# score_anzeige.net
KiCad netlist of a schematic drawn in EAGLE
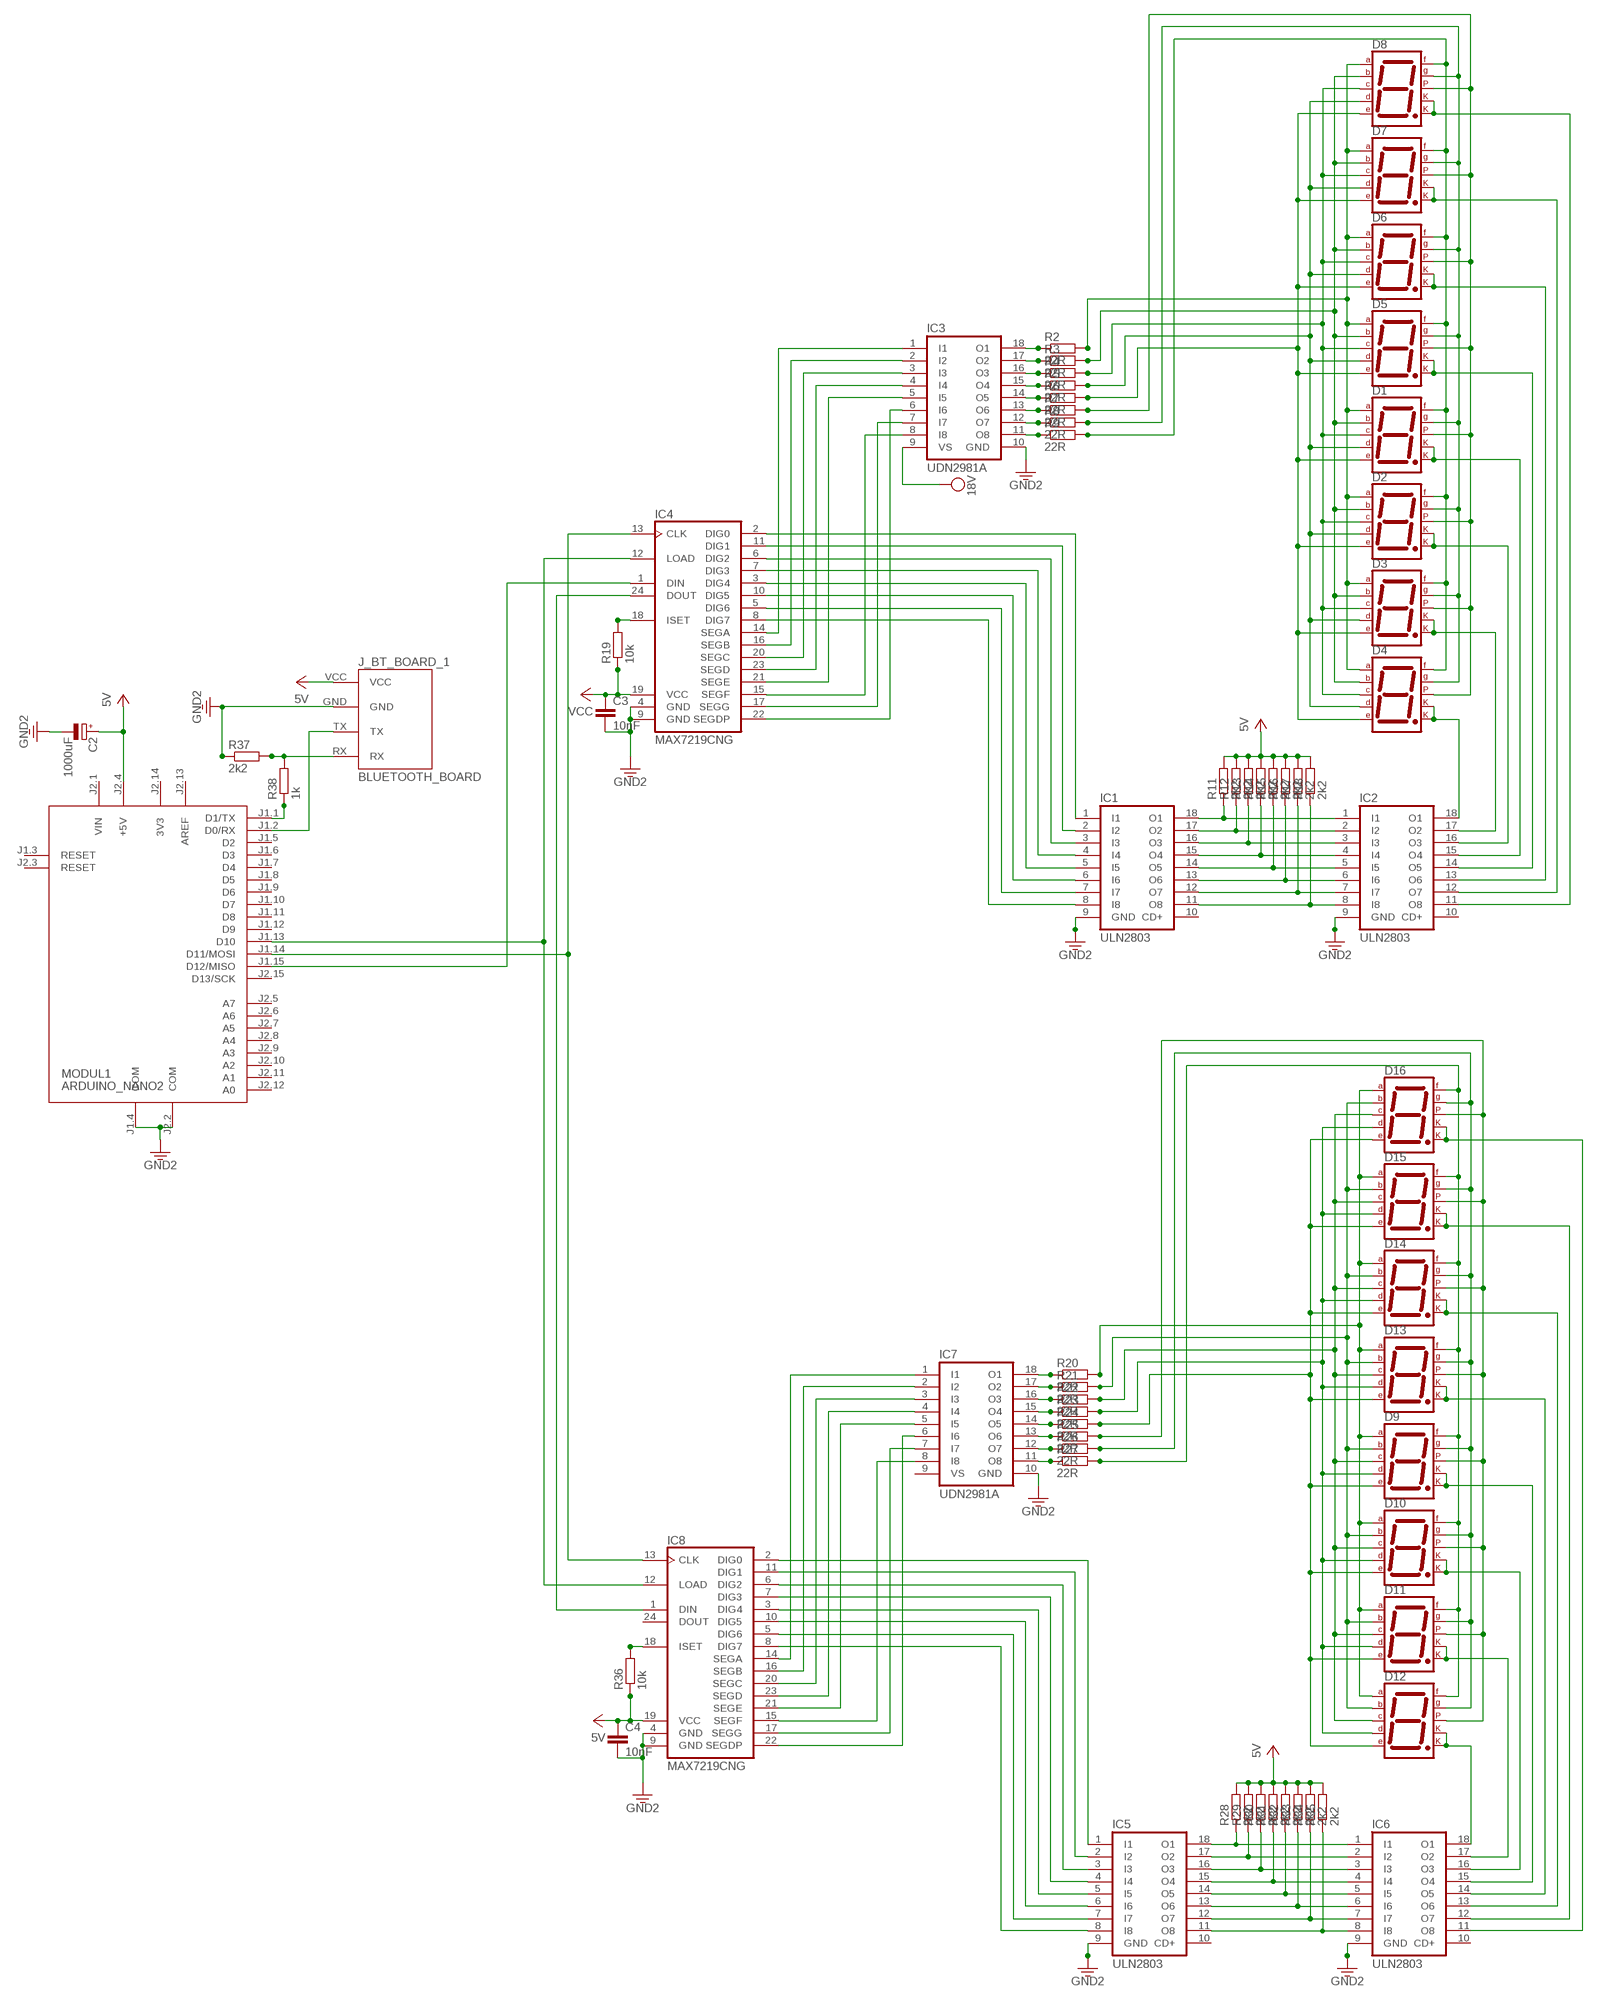
[diagram p0: schematic, sheet 1]

(export (version "E")
  (design (tool "Eeschema 10.0.6"))
  (components
    (comp (ref "C2")
      (value "1000uF")
      (footprint "eagle-import:E5-10,5")
      (libsource (lib "eagle-import") (part "CPOL-EUE5-10.5"))
    )
    (comp (ref "C3")
      (value "10nF")
      (footprint "eagle-import:C025-025X050")
      (libsource (lib "eagle-import") (part "C-EU025-025X050"))
    )
    (comp (ref "C4")
      (value "10nF")
      (footprint "eagle-import:C025-025X050")
      (libsource (lib "eagle-import") (part "C-EU025-025X050"))
    )
    (comp (ref "D1")
      (value "7SEG-MCK")
      (footprint "eagle-import:7SEG-7")
      (libsource (lib "eagle-import") (part "7SEG-MCK"))
    )
    (comp (ref "D2")
      (value "7SEG-MCK")
      (footprint "eagle-import:7SEG-7")
      (libsource (lib "eagle-import") (part "7SEG-MCK"))
    )
    (comp (ref "D3")
      (value "7SEG-MCK")
      (footprint "eagle-import:7SEG-7")
      (libsource (lib "eagle-import") (part "7SEG-MCK"))
    )
    (comp (ref "D4")
      (value "7SEG-MCK")
      (footprint "eagle-import:7SEG-7")
      (libsource (lib "eagle-import") (part "7SEG-MCK"))
    )
    (comp (ref "D5")
      (value "7SEG-MCK")
      (footprint "eagle-import:7SEG-7")
      (libsource (lib "eagle-import") (part "7SEG-MCK"))
    )
    (comp (ref "D6")
      (value "7SEG-MCK")
      (footprint "eagle-import:7SEG-7")
      (libsource (lib "eagle-import") (part "7SEG-MCK"))
    )
    (comp (ref "D7")
      (value "7SEG-MCK")
      (footprint "eagle-import:7SEG-7")
      (libsource (lib "eagle-import") (part "7SEG-MCK"))
    )
    (comp (ref "D8")
      (value "7SEG-MCK")
      (footprint "eagle-import:7SEG-7")
      (libsource (lib "eagle-import") (part "7SEG-MCK"))
    )
    (comp (ref "D9")
      (value "7SEG-MCK")
      (footprint "eagle-import:7SEG-7")
      (libsource (lib "eagle-import") (part "7SEG-MCK"))
    )
    (comp (ref "D10")
      (value "7SEG-MCK")
      (footprint "eagle-import:7SEG-7")
      (libsource (lib "eagle-import") (part "7SEG-MCK"))
    )
    (comp (ref "D11")
      (value "7SEG-MCK")
      (footprint "eagle-import:7SEG-7")
      (libsource (lib "eagle-import") (part "7SEG-MCK"))
    )
    (comp (ref "D12")
      (value "7SEG-MCK")
      (footprint "eagle-import:7SEG-7")
      (libsource (lib "eagle-import") (part "7SEG-MCK"))
    )
    (comp (ref "D13")
      (value "7SEG-MCK")
      (footprint "eagle-import:7SEG-7")
      (libsource (lib "eagle-import") (part "7SEG-MCK"))
    )
    (comp (ref "D14")
      (value "7SEG-MCK")
      (footprint "eagle-import:7SEG-7")
      (libsource (lib "eagle-import") (part "7SEG-MCK"))
    )
    (comp (ref "D15")
      (value "7SEG-MCK")
      (footprint "eagle-import:7SEG-7")
      (libsource (lib "eagle-import") (part "7SEG-MCK"))
    )
    (comp (ref "D16")
      (value "7SEG-MCK")
      (footprint "eagle-import:7SEG-7")
      (libsource (lib "eagle-import") (part "7SEG-MCK"))
    )
    (comp (ref "IC1")
      (value "ULN2803")
      (footprint "eagle-import:DIL18")
      (libsource (lib "eagle-import") (part "ULN2803A"))
    )
    (comp (ref "IC2")
      (value "ULN2803")
      (footprint "eagle-import:DIL18")
      (libsource (lib "eagle-import") (part "ULN2803A"))
    )
    (comp (ref "IC3")
      (value "UDN2981A")
      (footprint "eagle-import:DIL18")
      (libsource (lib "eagle-import") (part "UDN298A1"))
    )
    (comp (ref "IC4")
      (value "MAX7219CNG")
      (footprint "eagle-import:DIL24-3")
      (fields (field (name "MF") "MAXIM"))
      (libsource (lib "eagle-import") (part "MAX7219CNG"))
    )
    (comp (ref "IC5")
      (value "ULN2803")
      (footprint "eagle-import:DIL18")
      (libsource (lib "eagle-import") (part "ULN2803A"))
    )
    (comp (ref "IC6")
      (value "ULN2803")
      (footprint "eagle-import:DIL18")
      (libsource (lib "eagle-import") (part "ULN2803A"))
    )
    (comp (ref "IC7")
      (value "UDN2981A")
      (footprint "eagle-import:DIL18")
      (libsource (lib "eagle-import") (part "UDN298A1"))
    )
    (comp (ref "IC8")
      (value "MAX7219CNG")
      (footprint "eagle-import:DIL24-3")
      (fields (field (name "MF") "MAXIM"))
      (libsource (lib "eagle-import") (part "MAX7219CNG"))
    )
    (comp (ref "J_BT_BOARD_1")
      (value "BLUETOOTH_BOARD")
      (footprint "eagle-import:BT_BOARD_FOOTPRINT")
      (libsource (lib "eagle-import") (part "BLUETOOTH_BOARD"))
    )
    (comp (ref "MODUL1")
      (value "ARDUINO_NANO2")
      (footprint "eagle-import:ARDUINO_NANO2")
      (libsource (lib "eagle-import") (part "ARDUINO_NANO2"))
    )
    (comp (ref "R2")
      (value "22R")
      (footprint "eagle-import:0204_7")
      (libsource (lib "eagle-import") (part "R-EU_0204/7"))
    )
    (comp (ref "R3")
      (value "22R")
      (footprint "eagle-import:0204_7")
      (libsource (lib "eagle-import") (part "R-EU_0204/7"))
    )
    (comp (ref "R4")
      (value "22R")
      (footprint "eagle-import:0204_7")
      (libsource (lib "eagle-import") (part "R-EU_0204/7"))
    )
    (comp (ref "R5")
      (value "22R")
      (footprint "eagle-import:0204_7")
      (libsource (lib "eagle-import") (part "R-EU_0204/7"))
    )
    (comp (ref "R6")
      (value "22R")
      (footprint "eagle-import:0204_7")
      (libsource (lib "eagle-import") (part "R-EU_0204/7"))
    )
    (comp (ref "R7")
      (value "22R")
      (footprint "eagle-import:0204_7")
      (libsource (lib "eagle-import") (part "R-EU_0204/7"))
    )
    (comp (ref "R8")
      (value "22R")
      (footprint "eagle-import:0204_7")
      (libsource (lib "eagle-import") (part "R-EU_0204/7"))
    )
    (comp (ref "R9")
      (value "22R")
      (footprint "eagle-import:0204_7")
      (libsource (lib "eagle-import") (part "R-EU_0204/7"))
    )
    (comp (ref "R11")
      (value "2k2")
      (footprint "eagle-import:0204_7")
      (libsource (lib "eagle-import") (part "R-EU_0204/7"))
    )
    (comp (ref "R12")
      (value "2k2")
      (footprint "eagle-import:0204_7")
      (libsource (lib "eagle-import") (part "R-EU_0204/7"))
    )
    (comp (ref "R13")
      (value "2k2")
      (footprint "eagle-import:0204_7")
      (libsource (lib "eagle-import") (part "R-EU_0204/7"))
    )
    (comp (ref "R14")
      (value "2k2")
      (footprint "eagle-import:0204_7")
      (libsource (lib "eagle-import") (part "R-EU_0204/7"))
    )
    (comp (ref "R15")
      (value "2k2")
      (footprint "eagle-import:0204_7")
      (libsource (lib "eagle-import") (part "R-EU_0204/7"))
    )
    (comp (ref "R16")
      (value "2k2")
      (footprint "eagle-import:0204_7")
      (libsource (lib "eagle-import") (part "R-EU_0204/7"))
    )
    (comp (ref "R17")
      (value "2k2")
      (footprint "eagle-import:0204_7")
      (libsource (lib "eagle-import") (part "R-EU_0204/7"))
    )
    (comp (ref "R18")
      (value "2k2")
      (footprint "eagle-import:0204_7")
      (libsource (lib "eagle-import") (part "R-EU_0204/7"))
    )
    (comp (ref "R19")
      (value "10k")
      (footprint "eagle-import:0204_7")
      (libsource (lib "eagle-import") (part "R-EU_0204/7"))
    )
    (comp (ref "R20")
      (value "22R")
      (footprint "eagle-import:0204_7")
      (libsource (lib "eagle-import") (part "R-EU_0204/7"))
    )
    (comp (ref "R21")
      (value "22R")
      (footprint "eagle-import:0204_7")
      (libsource (lib "eagle-import") (part "R-EU_0204/7"))
    )
    (comp (ref "R22")
      (value "22R")
      (footprint "eagle-import:0204_7")
      (libsource (lib "eagle-import") (part "R-EU_0204/7"))
    )
    (comp (ref "R23")
      (value "22R")
      (footprint "eagle-import:0204_7")
      (libsource (lib "eagle-import") (part "R-EU_0204/7"))
    )
    (comp (ref "R24")
      (value "22R")
      (footprint "eagle-import:0204_7")
      (libsource (lib "eagle-import") (part "R-EU_0204/7"))
    )
    (comp (ref "R25")
      (value "22R")
      (footprint "eagle-import:0204_7")
      (libsource (lib "eagle-import") (part "R-EU_0204/7"))
    )
    (comp (ref "R26")
      (value "22R")
      (footprint "eagle-import:0204_7")
      (libsource (lib "eagle-import") (part "R-EU_0204/7"))
    )
    (comp (ref "R27")
      (value "22R")
      (footprint "eagle-import:0204_7")
      (libsource (lib "eagle-import") (part "R-EU_0204/7"))
    )
    (comp (ref "R28")
      (value "2k2")
      (footprint "eagle-import:0204_7")
      (libsource (lib "eagle-import") (part "R-EU_0204/7"))
    )
    (comp (ref "R29")
      (value "2k2")
      (footprint "eagle-import:0204_7")
      (libsource (lib "eagle-import") (part "R-EU_0204/7"))
    )
    (comp (ref "R30")
      (value "2k2")
      (footprint "eagle-import:0204_7")
      (libsource (lib "eagle-import") (part "R-EU_0204/7"))
    )
    (comp (ref "R31")
      (value "2k2")
      (footprint "eagle-import:0204_7")
      (libsource (lib "eagle-import") (part "R-EU_0204/7"))
    )
    (comp (ref "R32")
      (value "2k2")
      (footprint "eagle-import:0204_7")
      (libsource (lib "eagle-import") (part "R-EU_0204/7"))
    )
    (comp (ref "R33")
      (value "2k2")
      (footprint "eagle-import:0204_7")
      (libsource (lib "eagle-import") (part "R-EU_0204/7"))
    )
    (comp (ref "R34")
      (value "2k2")
      (footprint "eagle-import:0204_7")
      (libsource (lib "eagle-import") (part "R-EU_0204/7"))
    )
    (comp (ref "R35")
      (value "2k2")
      (footprint "eagle-import:0204_7")
      (libsource (lib "eagle-import") (part "R-EU_0204/7"))
    )
    (comp (ref "R36")
      (value "10k")
      (footprint "eagle-import:0204_7")
      (libsource (lib "eagle-import") (part "R-EU_0204/7"))
    )
    (comp (ref "R37")
      (value "2k2")
      (footprint "eagle-import:0204_7")
      (libsource (lib "eagle-import") (part "R-EU_0204/7"))
    )
    (comp (ref "R38")
      (value "1k")
      (footprint "eagle-import:0204_7")
      (libsource (lib "eagle-import") (part "R-EU_0204/7"))
    )
  )
  (nets
    (net (code "1") (name "/3V3") (class "Default")
      (node (ref "MODUL1") (pin "J2.14") (pinfunction "3V3_J2.14") (pintype "power_in"))
    )
    (net (code "2") (name "/AREF") (class "Default")
      (node (ref "MODUL1") (pin "J2.13") (pinfunction "AREF_J2.13") (pintype "power_in"))
    )
    (net (code "3") (name "/VIN") (class "Default")
      (node (ref "MODUL1") (pin "J2.1") (pinfunction "VIN_J2.1") (pintype "power_in"))
    )
    (net (code "4") (name "18V") (class "Default")
      (node (ref "C2") (pin "+") (pinfunction "+_+") (pintype "passive"))
      (node (ref "C3") (pin "1") (pinfunction "1_1") (pintype "passive"))
      (node (ref "C4") (pin "1") (pinfunction "1_1") (pintype "passive"))
      (node (ref "IC3") (pin "9") (pinfunction "VS_9") (pintype "passive"))
      (node (ref "IC4") (pin "19") (pinfunction "VCC_19") (pintype "power_in"))
      (node (ref "IC8") (pin "19") (pinfunction "VCC_19") (pintype "power_in"))
      (node (ref "J_BT_BOARD_1") (pin "VCC") (pinfunction "VCC_VCC") (pintype "bidirectional"))
      (node (ref "MODUL1") (pin "J2.4") (pinfunction "+5V_J2.4") (pintype "power_in"))
      (node (ref "R11") (pin "2") (pinfunction "2_2") (pintype "passive"))
      (node (ref "R12") (pin "2") (pinfunction "2_2") (pintype "passive"))
      (node (ref "R13") (pin "2") (pinfunction "2_2") (pintype "passive"))
      (node (ref "R14") (pin "2") (pinfunction "2_2") (pintype "passive"))
      (node (ref "R15") (pin "2") (pinfunction "2_2") (pintype "passive"))
      (node (ref "R16") (pin "2") (pinfunction "2_2") (pintype "passive"))
      (node (ref "R17") (pin "2") (pinfunction "2_2") (pintype "passive"))
      (node (ref "R18") (pin "2") (pinfunction "2_2") (pintype "passive"))
      (node (ref "R19") (pin "1") (pinfunction "1_1") (pintype "passive"))
      (node (ref "R28") (pin "2") (pinfunction "2_2") (pintype "passive"))
      (node (ref "R29") (pin "2") (pinfunction "2_2") (pintype "passive"))
      (node (ref "R30") (pin "2") (pinfunction "2_2") (pintype "passive"))
      (node (ref "R31") (pin "2") (pinfunction "2_2") (pintype "passive"))
      (node (ref "R32") (pin "2") (pinfunction "2_2") (pintype "passive"))
      (node (ref "R33") (pin "2") (pinfunction "2_2") (pintype "passive"))
      (node (ref "R34") (pin "2") (pinfunction "2_2") (pintype "passive"))
      (node (ref "R35") (pin "2") (pinfunction "2_2") (pintype "passive"))
      (node (ref "R36") (pin "1") (pinfunction "1_1") (pintype "passive"))
    )
    (net (code "5") (name "GND2") (class "Default")
      (node (ref "C2") (pin "-") (pinfunction "-_-") (pintype "passive"))
      (node (ref "C3") (pin "2") (pinfunction "2_2") (pintype "passive"))
      (node (ref "C4") (pin "2") (pinfunction "2_2") (pintype "passive"))
      (node (ref "IC1") (pin "9") (pinfunction "GND_9") (pintype "power_in"))
      (node (ref "IC2") (pin "9") (pinfunction "GND_9") (pintype "power_in"))
      (node (ref "IC3") (pin "10") (pinfunction "GND_10") (pintype "power_in"))
      (node (ref "IC4") (pin "4") (pinfunction "GND_4") (pintype "power_in"))
      (node (ref "IC4") (pin "9") (pinfunction "GND_9") (pintype "power_in"))
      (node (ref "IC5") (pin "9") (pinfunction "GND_9") (pintype "power_in"))
      (node (ref "IC6") (pin "9") (pinfunction "GND_9") (pintype "power_in"))
      (node (ref "IC7") (pin "10") (pinfunction "GND_10") (pintype "power_in"))
      (node (ref "IC8") (pin "4") (pinfunction "GND_4") (pintype "power_in"))
      (node (ref "IC8") (pin "9") (pinfunction "GND_9") (pintype "power_in"))
      (node (ref "J_BT_BOARD_1") (pin "GND") (pinfunction "GND_GND") (pintype "bidirectional"))
      (node (ref "MODUL1") (pin "J1.4") (pinfunction "COM_J1.4") (pintype "power_in"))
      (node (ref "MODUL1") (pin "J2.2") (pinfunction "COM_J2.2") (pintype "power_in"))
      (node (ref "R37") (pin "1") (pinfunction "1_1") (pintype "passive"))
    )
    (net (code "6") (name "Net-(D1-A)") (class "Default")
      (node (ref "D1") (pin "10") (pinfunction "A_10") (pintype "passive"))
      (node (ref "D2") (pin "10") (pinfunction "A_10") (pintype "passive"))
      (node (ref "D3") (pin "10") (pinfunction "A_10") (pintype "passive"))
      (node (ref "D4") (pin "10") (pinfunction "A_10") (pintype "passive"))
      (node (ref "D5") (pin "10") (pinfunction "A_10") (pintype "passive"))
      (node (ref "D6") (pin "10") (pinfunction "A_10") (pintype "passive"))
      (node (ref "D7") (pin "10") (pinfunction "A_10") (pintype "passive"))
      (node (ref "D8") (pin "10") (pinfunction "A_10") (pintype "passive"))
      (node (ref "R2") (pin "2") (pinfunction "2_2") (pintype "passive"))
    )
    (net (code "7") (name "Net-(D1-B)") (class "Default")
      (node (ref "D1") (pin "9") (pinfunction "B_9") (pintype "passive"))
      (node (ref "D2") (pin "9") (pinfunction "B_9") (pintype "passive"))
      (node (ref "D3") (pin "9") (pinfunction "B_9") (pintype "passive"))
      (node (ref "D4") (pin "9") (pinfunction "B_9") (pintype "passive"))
      (node (ref "D5") (pin "9") (pinfunction "B_9") (pintype "passive"))
      (node (ref "D6") (pin "9") (pinfunction "B_9") (pintype "passive"))
      (node (ref "D7") (pin "9") (pinfunction "B_9") (pintype "passive"))
      (node (ref "D8") (pin "9") (pinfunction "B_9") (pintype "passive"))
      (node (ref "R3") (pin "2") (pinfunction "2_2") (pintype "passive"))
    )
    (net (code "8") (name "Net-(D1-C)") (class "Default")
      (node (ref "D1") (pin "8") (pinfunction "C_8") (pintype "passive"))
      (node (ref "D2") (pin "8") (pinfunction "C_8") (pintype "passive"))
      (node (ref "D3") (pin "8") (pinfunction "C_8") (pintype "passive"))
      (node (ref "D4") (pin "8") (pinfunction "C_8") (pintype "passive"))
      (node (ref "D5") (pin "8") (pinfunction "C_8") (pintype "passive"))
      (node (ref "D6") (pin "8") (pinfunction "C_8") (pintype "passive"))
      (node (ref "D7") (pin "8") (pinfunction "C_8") (pintype "passive"))
      (node (ref "D8") (pin "8") (pinfunction "C_8") (pintype "passive"))
      (node (ref "R4") (pin "2") (pinfunction "2_2") (pintype "passive"))
    )
    (net (code "9") (name "Net-(D1-CK1)") (class "Default")
      (node (ref "D1") (pin "1") (pinfunction "CK1_1") (pintype "passive"))
      (node (ref "D1") (pin "6") (pinfunction "CK2_6") (pintype "passive"))
      (node (ref "IC2") (pin "15") (pinfunction "O4_15") (pintype "open_collector"))
    )
    (net (code "10") (name "Net-(D1-D)") (class "Default")
      (node (ref "D1") (pin "5") (pinfunction "D_5") (pintype "passive"))
      (node (ref "D2") (pin "5") (pinfunction "D_5") (pintype "passive"))
      (node (ref "D3") (pin "5") (pinfunction "D_5") (pintype "passive"))
      (node (ref "D4") (pin "5") (pinfunction "D_5") (pintype "passive"))
      (node (ref "D5") (pin "5") (pinfunction "D_5") (pintype "passive"))
      (node (ref "D6") (pin "5") (pinfunction "D_5") (pintype "passive"))
      (node (ref "D7") (pin "5") (pinfunction "D_5") (pintype "passive"))
      (node (ref "D8") (pin "5") (pinfunction "D_5") (pintype "passive"))
      (node (ref "R5") (pin "2") (pinfunction "2_2") (pintype "passive"))
    )
    (net (code "11") (name "Net-(D1-DP)") (class "Default")
      (node (ref "D1") (pin "7") (pinfunction "DP_7") (pintype "passive"))
      (node (ref "D2") (pin "7") (pinfunction "DP_7") (pintype "passive"))
      (node (ref "D3") (pin "7") (pinfunction "DP_7") (pintype "passive"))
      (node (ref "D4") (pin "7") (pinfunction "DP_7") (pintype "passive"))
      (node (ref "D5") (pin "7") (pinfunction "DP_7") (pintype "passive"))
      (node (ref "D6") (pin "7") (pinfunction "DP_7") (pintype "passive"))
      (node (ref "D7") (pin "7") (pinfunction "DP_7") (pintype "passive"))
      (node (ref "D8") (pin "7") (pinfunction "DP_7") (pintype "passive"))
      (node (ref "R7") (pin "2") (pinfunction "2_2") (pintype "passive"))
    )
    (net (code "12") (name "Net-(D1-E)") (class "Default")
      (node (ref "D1") (pin "4") (pinfunction "E_4") (pintype "passive"))
      (node (ref "D2") (pin "4") (pinfunction "E_4") (pintype "passive"))
      (node (ref "D3") (pin "4") (pinfunction "E_4") (pintype "passive"))
      (node (ref "D4") (pin "4") (pinfunction "E_4") (pintype "passive"))
      (node (ref "D5") (pin "4") (pinfunction "E_4") (pintype "passive"))
      (node (ref "D6") (pin "4") (pinfunction "E_4") (pintype "passive"))
      (node (ref "D7") (pin "4") (pinfunction "E_4") (pintype "passive"))
      (node (ref "D8") (pin "4") (pinfunction "E_4") (pintype "passive"))
      (node (ref "R6") (pin "2") (pinfunction "2_2") (pintype "passive"))
    )
    (net (code "13") (name "Net-(D1-F)") (class "Default")
      (node (ref "D1") (pin "2") (pinfunction "F_2") (pintype "passive"))
      (node (ref "D2") (pin "2") (pinfunction "F_2") (pintype "passive"))
      (node (ref "D3") (pin "2") (pinfunction "F_2") (pintype "passive"))
      (node (ref "D4") (pin "2") (pinfunction "F_2") (pintype "passive"))
      (node (ref "D5") (pin "2") (pinfunction "F_2") (pintype "passive"))
      (node (ref "D6") (pin "2") (pinfunction "F_2") (pintype "passive"))
      (node (ref "D7") (pin "2") (pinfunction "F_2") (pintype "passive"))
      (node (ref "D8") (pin "2") (pinfunction "F_2") (pintype "passive"))
      (node (ref "R9") (pin "2") (pinfunction "2_2") (pintype "passive"))
    )
    (net (code "14") (name "Net-(D1-G)") (class "Default")
      (node (ref "D1") (pin "3") (pinfunction "G_3") (pintype "passive"))
      (node (ref "D2") (pin "3") (pinfunction "G_3") (pintype "passive"))
      (node (ref "D3") (pin "3") (pinfunction "G_3") (pintype "passive"))
      (node (ref "D4") (pin "3") (pinfunction "G_3") (pintype "passive"))
      (node (ref "D5") (pin "3") (pinfunction "G_3") (pintype "passive"))
      (node (ref "D6") (pin "3") (pinfunction "G_3") (pintype "passive"))
      (node (ref "D7") (pin "3") (pinfunction "G_3") (pintype "passive"))
      (node (ref "D8") (pin "3") (pinfunction "G_3") (pintype "passive"))
      (node (ref "R8") (pin "2") (pinfunction "2_2") (pintype "passive"))
    )
    (net (code "15") (name "Net-(D2-CK1)") (class "Default")
      (node (ref "D2") (pin "1") (pinfunction "CK1_1") (pintype "passive"))
      (node (ref "D2") (pin "6") (pinfunction "CK2_6") (pintype "passive"))
      (node (ref "IC2") (pin "16") (pinfunction "O3_16") (pintype "open_collector"))
    )
    (net (code "16") (name "Net-(D3-CK1)") (class "Default")
      (node (ref "D3") (pin "1") (pinfunction "CK1_1") (pintype "passive"))
      (node (ref "D3") (pin "6") (pinfunction "CK2_6") (pintype "passive"))
      (node (ref "IC2") (pin "17") (pinfunction "O2_17") (pintype "open_collector"))
    )
    (net (code "17") (name "Net-(D4-CK1)") (class "Default")
      (node (ref "D4") (pin "1") (pinfunction "CK1_1") (pintype "passive"))
      (node (ref "D4") (pin "6") (pinfunction "CK2_6") (pintype "passive"))
      (node (ref "IC2") (pin "18") (pinfunction "O1_18") (pintype "open_collector"))
    )
    (net (code "18") (name "Net-(D5-CK1)") (class "Default")
      (node (ref "D5") (pin "1") (pinfunction "CK1_1") (pintype "passive"))
      (node (ref "D5") (pin "6") (pinfunction "CK2_6") (pintype "passive"))
      (node (ref "IC2") (pin "14") (pinfunction "O5_14") (pintype "open_collector"))
    )
    (net (code "19") (name "Net-(D6-CK1)") (class "Default")
      (node (ref "D6") (pin "1") (pinfunction "CK1_1") (pintype "passive"))
      (node (ref "D6") (pin "6") (pinfunction "CK2_6") (pintype "passive"))
      (node (ref "IC2") (pin "13") (pinfunction "O6_13") (pintype "open_collector"))
    )
    (net (code "20") (name "Net-(D7-CK1)") (class "Default")
      (node (ref "D7") (pin "1") (pinfunction "CK1_1") (pintype "passive"))
      (node (ref "D7") (pin "6") (pinfunction "CK2_6") (pintype "passive"))
      (node (ref "IC2") (pin "12") (pinfunction "O7_12") (pintype "open_collector"))
    )
    (net (code "21") (name "Net-(D8-CK1)") (class "Default")
      (node (ref "D8") (pin "1") (pinfunction "CK1_1") (pintype "passive"))
      (node (ref "D8") (pin "6") (pinfunction "CK2_6") (pintype "passive"))
      (node (ref "IC2") (pin "11") (pinfunction "O8_11") (pintype "open_collector"))
    )
    (net (code "22") (name "Net-(D9-CK1)") (class "Default")
      (node (ref "D9") (pin "1") (pinfunction "CK1_1") (pintype "passive"))
      (node (ref "D9") (pin "6") (pinfunction "CK2_6") (pintype "passive"))
      (node (ref "IC6") (pin "15") (pinfunction "O4_15") (pintype "open_collector"))
    )
    (net (code "23") (name "Net-(D10-A)") (class "Default")
      (node (ref "D10") (pin "10") (pinfunction "A_10") (pintype "passive"))
      (node (ref "D11") (pin "10") (pinfunction "A_10") (pintype "passive"))
      (node (ref "D12") (pin "10") (pinfunction "A_10") (pintype "passive"))
      (node (ref "D13") (pin "10") (pinfunction "A_10") (pintype "passive"))
      (node (ref "D14") (pin "10") (pinfunction "A_10") (pintype "passive"))
      (node (ref "D15") (pin "10") (pinfunction "A_10") (pintype "passive"))
      (node (ref "D16") (pin "10") (pinfunction "A_10") (pintype "passive"))
      (node (ref "D9") (pin "10") (pinfunction "A_10") (pintype "passive"))
      (node (ref "R20") (pin "2") (pinfunction "2_2") (pintype "passive"))
    )
    (net (code "24") (name "Net-(D10-B)") (class "Default")
      (node (ref "D10") (pin "9") (pinfunction "B_9") (pintype "passive"))
      (node (ref "D11") (pin "9") (pinfunction "B_9") (pintype "passive"))
      (node (ref "D12") (pin "9") (pinfunction "B_9") (pintype "passive"))
      (node (ref "D13") (pin "9") (pinfunction "B_9") (pintype "passive"))
      (node (ref "D14") (pin "9") (pinfunction "B_9") (pintype "passive"))
      (node (ref "D15") (pin "9") (pinfunction "B_9") (pintype "passive"))
      (node (ref "D16") (pin "9") (pinfunction "B_9") (pintype "passive"))
      (node (ref "D9") (pin "9") (pinfunction "B_9") (pintype "passive"))
      (node (ref "R21") (pin "2") (pinfunction "2_2") (pintype "passive"))
    )
    (net (code "25") (name "Net-(D10-C)") (class "Default")
      (node (ref "D10") (pin "8") (pinfunction "C_8") (pintype "passive"))
      (node (ref "D11") (pin "8") (pinfunction "C_8") (pintype "passive"))
      (node (ref "D12") (pin "8") (pinfunction "C_8") (pintype "passive"))
      (node (ref "D13") (pin "8") (pinfunction "C_8") (pintype "passive"))
      (node (ref "D14") (pin "8") (pinfunction "C_8") (pintype "passive"))
      (node (ref "D15") (pin "8") (pinfunction "C_8") (pintype "passive"))
      (node (ref "D16") (pin "8") (pinfunction "C_8") (pintype "passive"))
      (node (ref "D9") (pin "8") (pinfunction "C_8") (pintype "passive"))
      (node (ref "R22") (pin "2") (pinfunction "2_2") (pintype "passive"))
    )
    (net (code "26") (name "Net-(D10-CK1)") (class "Default")
      (node (ref "D10") (pin "1") (pinfunction "CK1_1") (pintype "passive"))
      (node (ref "D10") (pin "6") (pinfunction "CK2_6") (pintype "passive"))
      (node (ref "IC6") (pin "16") (pinfunction "O3_16") (pintype "open_collector"))
    )
    (net (code "27") (name "Net-(D10-D)") (class "Default")
      (node (ref "D10") (pin "5") (pinfunction "D_5") (pintype "passive"))
      (node (ref "D11") (pin "5") (pinfunction "D_5") (pintype "passive"))
      (node (ref "D12") (pin "5") (pinfunction "D_5") (pintype "passive"))
      (node (ref "D13") (pin "5") (pinfunction "D_5") (pintype "passive"))
      (node (ref "D14") (pin "5") (pinfunction "D_5") (pintype "passive"))
      (node (ref "D15") (pin "5") (pinfunction "D_5") (pintype "passive"))
      (node (ref "D16") (pin "5") (pinfunction "D_5") (pintype "passive"))
      (node (ref "D9") (pin "5") (pinfunction "D_5") (pintype "passive"))
      (node (ref "R23") (pin "2") (pinfunction "2_2") (pintype "passive"))
    )
    (net (code "28") (name "Net-(D10-DP)") (class "Default")
      (node (ref "D10") (pin "7") (pinfunction "DP_7") (pintype "passive"))
      (node (ref "D11") (pin "7") (pinfunction "DP_7") (pintype "passive"))
      (node (ref "D12") (pin "7") (pinfunction "DP_7") (pintype "passive"))
      (node (ref "D13") (pin "7") (pinfunction "DP_7") (pintype "passive"))
      (node (ref "D14") (pin "7") (pinfunction "DP_7") (pintype "passive"))
      (node (ref "D15") (pin "7") (pinfunction "DP_7") (pintype "passive"))
      (node (ref "D16") (pin "7") (pinfunction "DP_7") (pintype "passive"))
      (node (ref "D9") (pin "7") (pinfunction "DP_7") (pintype "passive"))
      (node (ref "R25") (pin "2") (pinfunction "2_2") (pintype "passive"))
    )
    (net (code "29") (name "Net-(D10-E)") (class "Default")
      (node (ref "D10") (pin "4") (pinfunction "E_4") (pintype "passive"))
      (node (ref "D11") (pin "4") (pinfunction "E_4") (pintype "passive"))
      (node (ref "D12") (pin "4") (pinfunction "E_4") (pintype "passive"))
      (node (ref "D13") (pin "4") (pinfunction "E_4") (pintype "passive"))
      (node (ref "D14") (pin "4") (pinfunction "E_4") (pintype "passive"))
      (node (ref "D15") (pin "4") (pinfunction "E_4") (pintype "passive"))
      (node (ref "D16") (pin "4") (pinfunction "E_4") (pintype "passive"))
      (node (ref "D9") (pin "4") (pinfunction "E_4") (pintype "passive"))
      (node (ref "R24") (pin "2") (pinfunction "2_2") (pintype "passive"))
    )
    (net (code "30") (name "Net-(D10-F)") (class "Default")
      (node (ref "D10") (pin "2") (pinfunction "F_2") (pintype "passive"))
      (node (ref "D11") (pin "2") (pinfunction "F_2") (pintype "passive"))
      (node (ref "D12") (pin "2") (pinfunction "F_2") (pintype "passive"))
      (node (ref "D13") (pin "2") (pinfunction "F_2") (pintype "passive"))
      (node (ref "D14") (pin "2") (pinfunction "F_2") (pintype "passive"))
      (node (ref "D15") (pin "2") (pinfunction "F_2") (pintype "passive"))
      (node (ref "D16") (pin "2") (pinfunction "F_2") (pintype "passive"))
      (node (ref "D9") (pin "2") (pinfunction "F_2") (pintype "passive"))
      (node (ref "R27") (pin "2") (pinfunction "2_2") (pintype "passive"))
    )
    (net (code "31") (name "Net-(D10-G)") (class "Default")
      (node (ref "D10") (pin "3") (pinfunction "G_3") (pintype "passive"))
      (node (ref "D11") (pin "3") (pinfunction "G_3") (pintype "passive"))
      (node (ref "D12") (pin "3") (pinfunction "G_3") (pintype "passive"))
      (node (ref "D13") (pin "3") (pinfunction "G_3") (pintype "passive"))
      (node (ref "D14") (pin "3") (pinfunction "G_3") (pintype "passive"))
      (node (ref "D15") (pin "3") (pinfunction "G_3") (pintype "passive"))
      (node (ref "D16") (pin "3") (pinfunction "G_3") (pintype "passive"))
      (node (ref "D9") (pin "3") (pinfunction "G_3") (pintype "passive"))
      (node (ref "R26") (pin "2") (pinfunction "2_2") (pintype "passive"))
    )
    (net (code "32") (name "Net-(D11-CK1)") (class "Default")
      (node (ref "D11") (pin "1") (pinfunction "CK1_1") (pintype "passive"))
      (node (ref "D11") (pin "6") (pinfunction "CK2_6") (pintype "passive"))
      (node (ref "IC6") (pin "17") (pinfunction "O2_17") (pintype "open_collector"))
    )
    (net (code "33") (name "Net-(D12-CK1)") (class "Default")
      (node (ref "D12") (pin "1") (pinfunction "CK1_1") (pintype "passive"))
      (node (ref "D12") (pin "6") (pinfunction "CK2_6") (pintype "passive"))
      (node (ref "IC6") (pin "18") (pinfunction "O1_18") (pintype "open_collector"))
    )
    (net (code "34") (name "Net-(D13-CK1)") (class "Default")
      (node (ref "D13") (pin "1") (pinfunction "CK1_1") (pintype "passive"))
      (node (ref "D13") (pin "6") (pinfunction "CK2_6") (pintype "passive"))
      (node (ref "IC6") (pin "14") (pinfunction "O5_14") (pintype "open_collector"))
    )
    (net (code "35") (name "Net-(D14-CK1)") (class "Default")
      (node (ref "D14") (pin "1") (pinfunction "CK1_1") (pintype "passive"))
      (node (ref "D14") (pin "6") (pinfunction "CK2_6") (pintype "passive"))
      (node (ref "IC6") (pin "13") (pinfunction "O6_13") (pintype "open_collector"))
    )
    (net (code "36") (name "Net-(D15-CK1)") (class "Default")
      (node (ref "D15") (pin "1") (pinfunction "CK1_1") (pintype "passive"))
      (node (ref "D15") (pin "6") (pinfunction "CK2_6") (pintype "passive"))
      (node (ref "IC6") (pin "12") (pinfunction "O7_12") (pintype "open_collector"))
    )
    (net (code "37") (name "Net-(D16-CK1)") (class "Default")
      (node (ref "D16") (pin "1") (pinfunction "CK1_1") (pintype "passive"))
      (node (ref "D16") (pin "6") (pinfunction "CK2_6") (pintype "passive"))
      (node (ref "IC6") (pin "11") (pinfunction "O8_11") (pintype "open_collector"))
    )
    (net (code "38") (name "Net-(IC1-I1)") (class "Default")
      (node (ref "IC1") (pin "1") (pinfunction "I1_1") (pintype "input"))
      (node (ref "IC4") (pin "2") (pinfunction "DIG0_2") (pintype "output"))
    )
    (net (code "39") (name "Net-(IC1-I2)") (class "Default")
      (node (ref "IC1") (pin "2") (pinfunction "I2_2") (pintype "input"))
      (node (ref "IC4") (pin "11") (pinfunction "DIG1_11") (pintype "output"))
    )
    (net (code "40") (name "Net-(IC1-I3)") (class "Default")
      (node (ref "IC1") (pin "3") (pinfunction "I3_3") (pintype "input"))
      (node (ref "IC4") (pin "6") (pinfunction "DIG2_6") (pintype "output"))
    )
    (net (code "41") (name "Net-(IC1-I4)") (class "Default")
      (node (ref "IC1") (pin "4") (pinfunction "I4_4") (pintype "input"))
      (node (ref "IC4") (pin "7") (pinfunction "DIG3_7") (pintype "output"))
    )
    (net (code "42") (name "Net-(IC1-I5)") (class "Default")
      (node (ref "IC1") (pin "5") (pinfunction "I5_5") (pintype "input"))
      (node (ref "IC4") (pin "3") (pinfunction "DIG4_3") (pintype "output"))
    )
    (net (code "43") (name "Net-(IC1-I6)") (class "Default")
      (node (ref "IC1") (pin "6") (pinfunction "I6_6") (pintype "input"))
      (node (ref "IC4") (pin "10") (pinfunction "DIG5_10") (pintype "output"))
    )
    (net (code "44") (name "Net-(IC1-I7)") (class "Default")
      (node (ref "IC1") (pin "7") (pinfunction "I7_7") (pintype "input"))
      (node (ref "IC4") (pin "5") (pinfunction "DIG6_5") (pintype "output"))
    )
    (net (code "45") (name "Net-(IC1-I8)") (class "Default")
      (node (ref "IC1") (pin "8") (pinfunction "I8_8") (pintype "input"))
      (node (ref "IC4") (pin "8") (pinfunction "DIG7_8") (pintype "output"))
    )
    (net (code "46") (name "Net-(IC1-O1)") (class "Default")
      (node (ref "IC1") (pin "18") (pinfunction "O1_18") (pintype "open_collector"))
      (node (ref "IC2") (pin "1") (pinfunction "I1_1") (pintype "input"))
      (node (ref "R11") (pin "1") (pinfunction "1_1") (pintype "passive"))
    )
    (net (code "47") (name "Net-(IC1-O2)") (class "Default")
      (node (ref "IC1") (pin "17") (pinfunction "O2_17") (pintype "open_collector"))
      (node (ref "IC2") (pin "2") (pinfunction "I2_2") (pintype "input"))
      (node (ref "R12") (pin "1") (pinfunction "1_1") (pintype "passive"))
    )
    (net (code "48") (name "Net-(IC1-O3)") (class "Default")
      (node (ref "IC1") (pin "16") (pinfunction "O3_16") (pintype "open_collector"))
      (node (ref "IC2") (pin "3") (pinfunction "I3_3") (pintype "input"))
      (node (ref "R13") (pin "1") (pinfunction "1_1") (pintype "passive"))
    )
    (net (code "49") (name "Net-(IC1-O4)") (class "Default")
      (node (ref "IC1") (pin "15") (pinfunction "O4_15") (pintype "open_collector"))
      (node (ref "IC2") (pin "4") (pinfunction "I4_4") (pintype "input"))
      (node (ref "R14") (pin "1") (pinfunction "1_1") (pintype "passive"))
    )
    (net (code "50") (name "Net-(IC1-O5)") (class "Default")
      (node (ref "IC1") (pin "14") (pinfunction "O5_14") (pintype "open_collector"))
      (node (ref "IC2") (pin "5") (pinfunction "I5_5") (pintype "input"))
      (node (ref "R15") (pin "1") (pinfunction "1_1") (pintype "passive"))
    )
    (net (code "51") (name "Net-(IC1-O6)") (class "Default")
      (node (ref "IC1") (pin "13") (pinfunction "O6_13") (pintype "open_collector"))
      (node (ref "IC2") (pin "6") (pinfunction "I6_6") (pintype "input"))
      (node (ref "R16") (pin "1") (pinfunction "1_1") (pintype "passive"))
    )
    (net (code "52") (name "Net-(IC1-O7)") (class "Default")
      (node (ref "IC1") (pin "12") (pinfunction "O7_12") (pintype "open_collector"))
      (node (ref "IC2") (pin "7") (pinfunction "I7_7") (pintype "input"))
      (node (ref "R17") (pin "1") (pinfunction "1_1") (pintype "passive"))
    )
    (net (code "53") (name "Net-(IC1-O8)") (class "Default")
      (node (ref "IC1") (pin "11") (pinfunction "O8_11") (pintype "open_collector"))
      (node (ref "IC2") (pin "8") (pinfunction "I8_8") (pintype "input"))
      (node (ref "R18") (pin "1") (pinfunction "1_1") (pintype "passive"))
    )
    (net (code "54") (name "Net-(IC3-I1)") (class "Default")
      (node (ref "IC3") (pin "1") (pinfunction "I1_1") (pintype "input"))
      (node (ref "IC4") (pin "14") (pinfunction "SEGA_14") (pintype "output"))
    )
    (net (code "55") (name "Net-(IC3-I2)") (class "Default")
      (node (ref "IC3") (pin "2") (pinfunction "I2_2") (pintype "input"))
      (node (ref "IC4") (pin "16") (pinfunction "SEGB_16") (pintype "output"))
    )
    (net (code "56") (name "Net-(IC3-I3)") (class "Default")
      (node (ref "IC3") (pin "3") (pinfunction "I3_3") (pintype "input"))
      (node (ref "IC4") (pin "20") (pinfunction "SEGC_20") (pintype "output"))
    )
    (net (code "57") (name "Net-(IC3-I4)") (class "Default")
      (node (ref "IC3") (pin "4") (pinfunction "I4_4") (pintype "input"))
      (node (ref "IC4") (pin "23") (pinfunction "SEGD_23") (pintype "output"))
    )
    (net (code "58") (name "Net-(IC3-I5)") (class "Default")
      (node (ref "IC3") (pin "5") (pinfunction "I5_5") (pintype "input"))
      (node (ref "IC4") (pin "21") (pinfunction "SEGE_21") (pintype "output"))
    )
    (net (code "59") (name "Net-(IC3-I6)") (class "Default")
      (node (ref "IC3") (pin "6") (pinfunction "I6_6") (pintype "input"))
      (node (ref "IC4") (pin "22") (pinfunction "SEGDP_22") (pintype "output"))
    )
    (net (code "60") (name "Net-(IC3-I7)") (class "Default")
      (node (ref "IC3") (pin "7") (pinfunction "I7_7") (pintype "input"))
      (node (ref "IC4") (pin "17") (pinfunction "SEGG_17") (pintype "output"))
    )
    (net (code "61") (name "Net-(IC3-I8)") (class "Default")
      (node (ref "IC3") (pin "8") (pinfunction "I8_8") (pintype "input"))
      (node (ref "IC4") (pin "15") (pinfunction "SEGF_15") (pintype "output"))
    )
    (net (code "62") (name "Net-(IC3-O1)") (class "Default")
      (node (ref "IC3") (pin "18") (pinfunction "O1_18") (pintype "open_collector"))
      (node (ref "R2") (pin "1") (pinfunction "1_1") (pintype "passive"))
    )
    (net (code "63") (name "Net-(IC3-O2)") (class "Default")
      (node (ref "IC3") (pin "17") (pinfunction "O2_17") (pintype "open_collector"))
      (node (ref "R3") (pin "1") (pinfunction "1_1") (pintype "passive"))
    )
    (net (code "64") (name "Net-(IC3-O3)") (class "Default")
      (node (ref "IC3") (pin "16") (pinfunction "O3_16") (pintype "open_collector"))
      (node (ref "R4") (pin "1") (pinfunction "1_1") (pintype "passive"))
    )
    (net (code "65") (name "Net-(IC3-O4)") (class "Default")
      (node (ref "IC3") (pin "15") (pinfunction "O4_15") (pintype "open_collector"))
      (node (ref "R5") (pin "1") (pinfunction "1_1") (pintype "passive"))
    )
    (net (code "66") (name "Net-(IC3-O5)") (class "Default")
      (node (ref "IC3") (pin "14") (pinfunction "O5_14") (pintype "open_collector"))
      (node (ref "R6") (pin "1") (pinfunction "1_1") (pintype "passive"))
    )
    (net (code "67") (name "Net-(IC3-O6)") (class "Default")
      (node (ref "IC3") (pin "13") (pinfunction "O6_13") (pintype "open_collector"))
      (node (ref "R7") (pin "1") (pinfunction "1_1") (pintype "passive"))
    )
    (net (code "68") (name "Net-(IC3-O7)") (class "Default")
      (node (ref "IC3") (pin "12") (pinfunction "O7_12") (pintype "open_collector"))
      (node (ref "R8") (pin "1") (pinfunction "1_1") (pintype "passive"))
    )
    (net (code "69") (name "Net-(IC3-O8)") (class "Default")
      (node (ref "IC3") (pin "11") (pinfunction "O8_11") (pintype "open_collector"))
      (node (ref "R9") (pin "1") (pinfunction "1_1") (pintype "passive"))
    )
    (net (code "70") (name "Net-(IC4-CLK)") (class "Default")
      (node (ref "IC4") (pin "13") (pinfunction "CLK_13") (pintype "input"))
      (node (ref "IC8") (pin "13") (pinfunction "CLK_13") (pintype "input"))
      (node (ref "MODUL1") (pin "J1.14") (pinfunction "D11/MOSI_J1.14") (pintype "bidirectional"))
    )
    (net (code "71") (name "Net-(IC4-DIN)") (class "Default")
      (node (ref "IC4") (pin "1") (pinfunction "DIN_1") (pintype "input"))
      (node (ref "MODUL1") (pin "J1.15") (pinfunction "D12/MISO_J1.15") (pintype "bidirectional"))
    )
    (net (code "72") (name "Net-(IC4-DOUT)") (class "Default")
      (node (ref "IC4") (pin "24") (pinfunction "DOUT_24") (pintype "output"))
      (node (ref "IC8") (pin "1") (pinfunction "DIN_1") (pintype "input"))
    )
    (net (code "73") (name "Net-(IC4-ISET)") (class "Default")
      (node (ref "IC4") (pin "18") (pinfunction "ISET_18") (pintype "input"))
      (node (ref "R19") (pin "2") (pinfunction "2_2") (pintype "passive"))
    )
    (net (code "74") (name "Net-(IC4-LOAD)") (class "Default")
      (node (ref "IC4") (pin "12") (pinfunction "LOAD_12") (pintype "input"))
      (node (ref "IC8") (pin "12") (pinfunction "LOAD_12") (pintype "input"))
      (node (ref "MODUL1") (pin "J1.13") (pinfunction "D10_J1.13") (pintype "bidirectional"))
    )
    (net (code "75") (name "Net-(IC5-I1)") (class "Default")
      (node (ref "IC5") (pin "1") (pinfunction "I1_1") (pintype "input"))
      (node (ref "IC8") (pin "2") (pinfunction "DIG0_2") (pintype "output"))
    )
    (net (code "76") (name "Net-(IC5-I2)") (class "Default")
      (node (ref "IC5") (pin "2") (pinfunction "I2_2") (pintype "input"))
      (node (ref "IC8") (pin "11") (pinfunction "DIG1_11") (pintype "output"))
    )
    (net (code "77") (name "Net-(IC5-I3)") (class "Default")
      (node (ref "IC5") (pin "3") (pinfunction "I3_3") (pintype "input"))
      (node (ref "IC8") (pin "6") (pinfunction "DIG2_6") (pintype "output"))
    )
    (net (code "78") (name "Net-(IC5-I4)") (class "Default")
      (node (ref "IC5") (pin "4") (pinfunction "I4_4") (pintype "input"))
      (node (ref "IC8") (pin "7") (pinfunction "DIG3_7") (pintype "output"))
    )
    (net (code "79") (name "Net-(IC5-I5)") (class "Default")
      (node (ref "IC5") (pin "5") (pinfunction "I5_5") (pintype "input"))
      (node (ref "IC8") (pin "3") (pinfunction "DIG4_3") (pintype "output"))
    )
    (net (code "80") (name "Net-(IC5-I6)") (class "Default")
      (node (ref "IC5") (pin "6") (pinfunction "I6_6") (pintype "input"))
      (node (ref "IC8") (pin "10") (pinfunction "DIG5_10") (pintype "output"))
    )
    (net (code "81") (name "Net-(IC5-I7)") (class "Default")
      (node (ref "IC5") (pin "7") (pinfunction "I7_7") (pintype "input"))
      (node (ref "IC8") (pin "5") (pinfunction "DIG6_5") (pintype "output"))
    )
    (net (code "82") (name "Net-(IC5-I8)") (class "Default")
      (node (ref "IC5") (pin "8") (pinfunction "I8_8") (pintype "input"))
      (node (ref "IC8") (pin "8") (pinfunction "DIG7_8") (pintype "output"))
    )
    (net (code "83") (name "Net-(IC5-O1)") (class "Default")
      (node (ref "IC5") (pin "18") (pinfunction "O1_18") (pintype "open_collector"))
      (node (ref "IC6") (pin "1") (pinfunction "I1_1") (pintype "input"))
      (node (ref "R28") (pin "1") (pinfunction "1_1") (pintype "passive"))
    )
    (net (code "84") (name "Net-(IC5-O2)") (class "Default")
      (node (ref "IC5") (pin "17") (pinfunction "O2_17") (pintype "open_collector"))
      (node (ref "IC6") (pin "2") (pinfunction "I2_2") (pintype "input"))
      (node (ref "R29") (pin "1") (pinfunction "1_1") (pintype "passive"))
    )
    (net (code "85") (name "Net-(IC5-O3)") (class "Default")
      (node (ref "IC5") (pin "16") (pinfunction "O3_16") (pintype "open_collector"))
      (node (ref "IC6") (pin "3") (pinfunction "I3_3") (pintype "input"))
      (node (ref "R30") (pin "1") (pinfunction "1_1") (pintype "passive"))
    )
    (net (code "86") (name "Net-(IC5-O4)") (class "Default")
      (node (ref "IC5") (pin "15") (pinfunction "O4_15") (pintype "open_collector"))
      (node (ref "IC6") (pin "4") (pinfunction "I4_4") (pintype "input"))
      (node (ref "R31") (pin "1") (pinfunction "1_1") (pintype "passive"))
    )
    (net (code "87") (name "Net-(IC5-O5)") (class "Default")
      (node (ref "IC5") (pin "14") (pinfunction "O5_14") (pintype "open_collector"))
      (node (ref "IC6") (pin "5") (pinfunction "I5_5") (pintype "input"))
      (node (ref "R32") (pin "1") (pinfunction "1_1") (pintype "passive"))
    )
    (net (code "88") (name "Net-(IC5-O6)") (class "Default")
      (node (ref "IC5") (pin "13") (pinfunction "O6_13") (pintype "open_collector"))
      (node (ref "IC6") (pin "6") (pinfunction "I6_6") (pintype "input"))
      (node (ref "R33") (pin "1") (pinfunction "1_1") (pintype "passive"))
    )
    (net (code "89") (name "Net-(IC5-O7)") (class "Default")
      (node (ref "IC5") (pin "12") (pinfunction "O7_12") (pintype "open_collector"))
      (node (ref "IC6") (pin "7") (pinfunction "I7_7") (pintype "input"))
      (node (ref "R34") (pin "1") (pinfunction "1_1") (pintype "passive"))
    )
    (net (code "90") (name "Net-(IC5-O8)") (class "Default")
      (node (ref "IC5") (pin "11") (pinfunction "O8_11") (pintype "open_collector"))
      (node (ref "IC6") (pin "8") (pinfunction "I8_8") (pintype "input"))
      (node (ref "R35") (pin "1") (pinfunction "1_1") (pintype "passive"))
    )
    (net (code "91") (name "Net-(IC7-I1)") (class "Default")
      (node (ref "IC7") (pin "1") (pinfunction "I1_1") (pintype "input"))
      (node (ref "IC8") (pin "14") (pinfunction "SEGA_14") (pintype "output"))
    )
    (net (code "92") (name "Net-(IC7-I2)") (class "Default")
      (node (ref "IC7") (pin "2") (pinfunction "I2_2") (pintype "input"))
      (node (ref "IC8") (pin "16") (pinfunction "SEGB_16") (pintype "output"))
    )
    (net (code "93") (name "Net-(IC7-I3)") (class "Default")
      (node (ref "IC7") (pin "3") (pinfunction "I3_3") (pintype "input"))
      (node (ref "IC8") (pin "20") (pinfunction "SEGC_20") (pintype "output"))
    )
    (net (code "94") (name "Net-(IC7-I4)") (class "Default")
      (node (ref "IC7") (pin "4") (pinfunction "I4_4") (pintype "input"))
      (node (ref "IC8") (pin "23") (pinfunction "SEGD_23") (pintype "output"))
    )
    (net (code "95") (name "Net-(IC7-I5)") (class "Default")
      (node (ref "IC7") (pin "5") (pinfunction "I5_5") (pintype "input"))
      (node (ref "IC8") (pin "21") (pinfunction "SEGE_21") (pintype "output"))
    )
    (net (code "96") (name "Net-(IC7-I6)") (class "Default")
      (node (ref "IC7") (pin "6") (pinfunction "I6_6") (pintype "input"))
      (node (ref "IC8") (pin "22") (pinfunction "SEGDP_22") (pintype "output"))
    )
    (net (code "97") (name "Net-(IC7-I7)") (class "Default")
      (node (ref "IC7") (pin "7") (pinfunction "I7_7") (pintype "input"))
      (node (ref "IC8") (pin "17") (pinfunction "SEGG_17") (pintype "output"))
    )
    (net (code "98") (name "Net-(IC7-I8)") (class "Default")
      (node (ref "IC7") (pin "8") (pinfunction "I8_8") (pintype "input"))
      (node (ref "IC8") (pin "15") (pinfunction "SEGF_15") (pintype "output"))
    )
    (net (code "99") (name "Net-(IC7-O1)") (class "Default")
      (node (ref "IC7") (pin "18") (pinfunction "O1_18") (pintype "open_collector"))
      (node (ref "R20") (pin "1") (pinfunction "1_1") (pintype "passive"))
    )
    (net (code "100") (name "Net-(IC7-O2)") (class "Default")
      (node (ref "IC7") (pin "17") (pinfunction "O2_17") (pintype "open_collector"))
      (node (ref "R21") (pin "1") (pinfunction "1_1") (pintype "passive"))
    )
    (net (code "101") (name "Net-(IC7-O3)") (class "Default")
      (node (ref "IC7") (pin "16") (pinfunction "O3_16") (pintype "open_collector"))
      (node (ref "R22") (pin "1") (pinfunction "1_1") (pintype "passive"))
    )
    (net (code "102") (name "Net-(IC7-O4)") (class "Default")
      (node (ref "IC7") (pin "15") (pinfunction "O4_15") (pintype "open_collector"))
      (node (ref "R23") (pin "1") (pinfunction "1_1") (pintype "passive"))
    )
    (net (code "103") (name "Net-(IC7-O5)") (class "Default")
      (node (ref "IC7") (pin "14") (pinfunction "O5_14") (pintype "open_collector"))
      (node (ref "R24") (pin "1") (pinfunction "1_1") (pintype "passive"))
    )
    (net (code "104") (name "Net-(IC7-O6)") (class "Default")
      (node (ref "IC7") (pin "13") (pinfunction "O6_13") (pintype "open_collector"))
      (node (ref "R25") (pin "1") (pinfunction "1_1") (pintype "passive"))
    )
    (net (code "105") (name "Net-(IC7-O7)") (class "Default")
      (node (ref "IC7") (pin "12") (pinfunction "O7_12") (pintype "open_collector"))
      (node (ref "R26") (pin "1") (pinfunction "1_1") (pintype "passive"))
    )
    (net (code "106") (name "Net-(IC7-O8)") (class "Default")
      (node (ref "IC7") (pin "11") (pinfunction "O8_11") (pintype "open_collector"))
      (node (ref "R27") (pin "1") (pinfunction "1_1") (pintype "passive"))
    )
    (net (code "107") (name "Net-(IC8-ISET)") (class "Default")
      (node (ref "IC8") (pin "18") (pinfunction "ISET_18") (pintype "input"))
      (node (ref "R36") (pin "2") (pinfunction "2_2") (pintype "passive"))
    )
    (net (code "108") (name "Net-(J_BT_BOARD_1-PadRX)") (class "Default")
      (node (ref "J_BT_BOARD_1") (pin "RX") (pinfunction "RX_RX") (pintype "bidirectional"))
      (node (ref "R37") (pin "2") (pinfunction "2_2") (pintype "passive"))
      (node (ref "R38") (pin "2") (pinfunction "2_2") (pintype "passive"))
    )
    (net (code "109") (name "Net-(MODUL1-D0{slash}RX)") (class "Default")
      (node (ref "J_BT_BOARD_1") (pin "TX") (pinfunction "TX_TX") (pintype "bidirectional"))
      (node (ref "MODUL1") (pin "J1.2") (pinfunction "D0/RX_J1.2") (pintype "bidirectional"))
    )
    (net (code "110") (name "Net-(MODUL1-D1{slash}TX)") (class "Default")
      (node (ref "MODUL1") (pin "J1.1") (pinfunction "D1/TX_J1.1") (pintype "bidirectional"))
      (node (ref "R38") (pin "1") (pinfunction "1_1") (pintype "passive"))
    )
    (net (code "111") (name "unconnected-(IC1-CD+-Pad10)") (class "Default")
      (node (ref "IC1") (pin "10") (pinfunction "CD+_10") (pintype "passive"))
    )
    (net (code "112") (name "unconnected-(IC2-CD+-Pad10)") (class "Default")
      (node (ref "IC2") (pin "10") (pinfunction "CD+_10") (pintype "passive"))
    )
    (net (code "113") (name "unconnected-(IC5-CD+-Pad10)") (class "Default")
      (node (ref "IC5") (pin "10") (pinfunction "CD+_10") (pintype "passive"))
    )
    (net (code "114") (name "unconnected-(IC6-CD+-Pad10)") (class "Default")
      (node (ref "IC6") (pin "10") (pinfunction "CD+_10") (pintype "passive"))
    )
    (net (code "115") (name "unconnected-(IC7-VS-Pad9)") (class "Default")
      (node (ref "IC7") (pin "9") (pinfunction "VS_9") (pintype "passive"))
    )
    (net (code "116") (name "unconnected-(IC8-DOUT-Pad24)") (class "Default")
      (node (ref "IC8") (pin "24") (pinfunction "DOUT_24") (pintype "output"))
    )
    (net (code "117") (name "unconnected-(MODUL1-A0-PadJ2.12)") (class "Default")
      (node (ref "MODUL1") (pin "J2.12") (pinfunction "A0_J2.12") (pintype "bidirectional"))
    )
    (net (code "118") (name "unconnected-(MODUL1-A1-PadJ2.11)") (class "Default")
      (node (ref "MODUL1") (pin "J2.11") (pinfunction "A1_J2.11") (pintype "bidirectional"))
    )
    (net (code "119") (name "unconnected-(MODUL1-A2-PadJ2.10)") (class "Default")
      (node (ref "MODUL1") (pin "J2.10") (pinfunction "A2_J2.10") (pintype "bidirectional"))
    )
    (net (code "120") (name "unconnected-(MODUL1-A3-PadJ2.9)") (class "Default")
      (node (ref "MODUL1") (pin "J2.9") (pinfunction "A3_J2.9") (pintype "bidirectional"))
    )
    (net (code "121") (name "unconnected-(MODUL1-A4-PadJ2.8)") (class "Default")
      (node (ref "MODUL1") (pin "J2.8") (pinfunction "A4_J2.8") (pintype "bidirectional"))
    )
    (net (code "122") (name "unconnected-(MODUL1-A5-PadJ2.7)") (class "Default")
      (node (ref "MODUL1") (pin "J2.7") (pinfunction "A5_J2.7") (pintype "bidirectional"))
    )
    (net (code "123") (name "unconnected-(MODUL1-A6-PadJ2.6)") (class "Default")
      (node (ref "MODUL1") (pin "J2.6") (pinfunction "A6_J2.6") (pintype "bidirectional"))
    )
    (net (code "124") (name "unconnected-(MODUL1-A7-PadJ2.5)") (class "Default")
      (node (ref "MODUL1") (pin "J2.5") (pinfunction "A7_J2.5") (pintype "bidirectional"))
    )
    (net (code "125") (name "unconnected-(MODUL1-D2-PadJ1.5)") (class "Default")
      (node (ref "MODUL1") (pin "J1.5") (pinfunction "D2_J1.5") (pintype "bidirectional"))
    )
    (net (code "126") (name "unconnected-(MODUL1-D3-PadJ1.6)") (class "Default")
      (node (ref "MODUL1") (pin "J1.6") (pinfunction "D3_J1.6") (pintype "bidirectional"))
    )
    (net (code "127") (name "unconnected-(MODUL1-D4-PadJ1.7)") (class "Default")
      (node (ref "MODUL1") (pin "J1.7") (pinfunction "D4_J1.7") (pintype "bidirectional"))
    )
    (net (code "128") (name "unconnected-(MODUL1-D5-PadJ1.8)") (class "Default")
      (node (ref "MODUL1") (pin "J1.8") (pinfunction "D5_J1.8") (pintype "bidirectional"))
    )
    (net (code "129") (name "unconnected-(MODUL1-D6-PadJ1.9)") (class "Default")
      (node (ref "MODUL1") (pin "J1.9") (pinfunction "D6_J1.9") (pintype "bidirectional"))
    )
    (net (code "130") (name "unconnected-(MODUL1-D7-PadJ1.10)") (class "Default")
      (node (ref "MODUL1") (pin "J1.10") (pinfunction "D7_J1.10") (pintype "bidirectional"))
    )
    (net (code "131") (name "unconnected-(MODUL1-D8-PadJ1.11)") (class "Default")
      (node (ref "MODUL1") (pin "J1.11") (pinfunction "D8_J1.11") (pintype "bidirectional"))
    )
    (net (code "132") (name "unconnected-(MODUL1-D9-PadJ1.12)") (class "Default")
      (node (ref "MODUL1") (pin "J1.12") (pinfunction "D9_J1.12") (pintype "bidirectional"))
    )
    (net (code "133") (name "unconnected-(MODUL1-D13{slash}SCK-PadJ2.15)") (class "Default")
      (node (ref "MODUL1") (pin "J2.15") (pinfunction "D13/SCK_J2.15") (pintype "bidirectional"))
    )
    (net (code "134") (name "unconnected-(MODUL1-RESET-PadJ1.3)") (class "Default")
      (node (ref "MODUL1") (pin "J1.3") (pinfunction "RESET_J1.3") (pintype "bidirectional"))
    )
    (net (code "135") (name "unconnected-(MODUL1-RESET-PadJ2.3)") (class "Default")
      (node (ref "MODUL1") (pin "J2.3") (pinfunction "RESET_J2.3") (pintype "bidirectional"))
    )
  )
)
